# bme_radar.net
KiCad netlist of a schematic drawn in Altium Designer
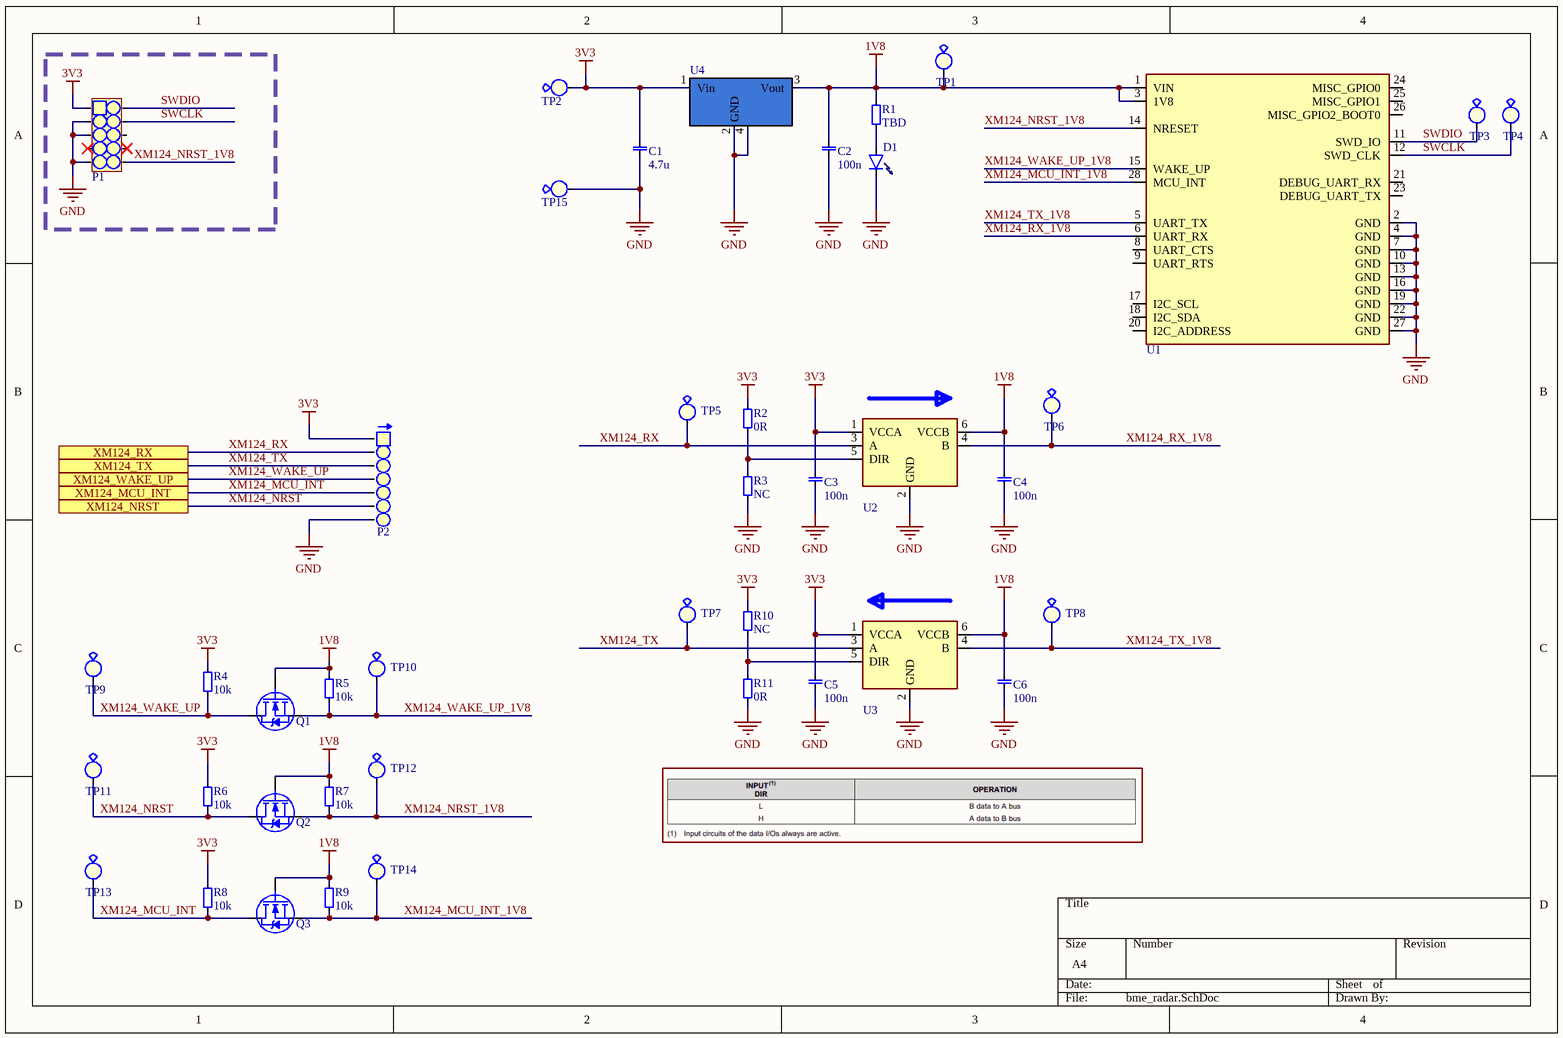
[diagram p0: bme_radar.SchDoc]

(export (version "E")
  (design (tool "Eeschema 10.0.6"))
  (components
    (comp (ref "C1")
      (value "4.7u")
      (footprint "0805, cap")
      (fields
        (field (name "MANUFACTURER PART NO") "CL21A475KAQNNNE")
        (field (name "Comment") "0805, capacitor")
      )
      (libsource (lib "jclib") (part "0805, capacitor"))
    )
    (comp (ref "C2")
      (value "100n")
      (footprint "0805, cap")
      (fields
        (field (name "MANUFACTURER PART NO") "C0805C104M5RAC7800")
        (field (name "Comment") "0805, capacitor")
      )
      (libsource (lib "jclib") (part "0805, capacitor"))
    )
    (comp (ref "C3")
      (value "100n")
      (footprint "0402 CAP")
      (fields
        (field (name "MANUFACTURER PART NO") "GRM155R62A104KE14D")
        (field (name "Comment") "0603, capacitor")
      )
      (libsource (lib "jclib") (part "0603, capacitor"))
    )
    (comp (ref "C4")
      (value "100n")
      (footprint "0402 CAP")
      (fields
        (field (name "MANUFACTURER PART NO") "GRM155R62A104KE14D")
        (field (name "Comment") "0603, capacitor")
      )
      (libsource (lib "jclib") (part "0603, capacitor"))
    )
    (comp (ref "C5")
      (value "100n")
      (footprint "0402 CAP")
      (fields
        (field (name "MANUFACTURER PART NO") "GRM155R62A104KE14D")
        (field (name "Comment") "0603, capacitor")
      )
      (libsource (lib "jclib") (part "0603, capacitor"))
    )
    (comp (ref "C6")
      (value "100n")
      (footprint "0402 CAP")
      (fields
        (field (name "MANUFACTURER PART NO") "GRM155R62A104KE14D")
        (field (name "Comment") "0603, capacitor")
      )
      (libsource (lib "jclib") (part "0603, capacitor"))
    )
    (comp (ref "D1")
      (value "0603, LED")
      (footprint "0603 LED")
      (fields (field (name "MANUFACTURER PART NO") "150060SS75003"))
      (libsource (lib "jclib") (part "0603, LED"))
    )
    (comp (ref "P1")
      (value "ARM 10 pin SWD")
      (footprint "FTSH-105-01-L-DV-K even odd")
      (description "1.27mm, PH")
      (fields (field (name "MANUFACTURER PART NO") "FTSH-105-01-L-DV-K"))
      (libsource (lib "jclib") (part "ARM 10 pin SWD"))
    )
    (comp (ref "P2")
      (value "1x7 Pin Header R/A")
      (footprint "1x7_HEADER_R/A")
      (description "1.27 mm")
      (fields (field (name "MANUFACTURER PART NO") "TMS-107-01-L-S-RA"))
      (libsource (lib "jclib") (part "1x7 Pin Header R/A"))
    )
    (comp (ref "Q1")
      (value "BSS138")
      (footprint "SOT323")
      (description "N-Channel Logic Level Enhancement Mode Field Effect Transistor")
      (fields (field (name "MANUFACTURER PART NO") "BSS138W-7-F"))
      (libsource (lib "jclib") (part "BSS138"))
    )
    (comp (ref "Q2")
      (value "BSS138")
      (footprint "SOT323")
      (description "N-Channel Logic Level Enhancement Mode Field Effect Transistor")
      (fields (field (name "MANUFACTURER PART NO") "BSS138W-7-F"))
      (libsource (lib "jclib") (part "BSS138"))
    )
    (comp (ref "Q3")
      (value "BSS138")
      (footprint "SOT323")
      (description "N-Channel Logic Level Enhancement Mode Field Effect Transistor")
      (fields (field (name "MANUFACTURER PART NO") "BSS138W-7-F"))
      (libsource (lib "jclib") (part "BSS138"))
    )
    (comp (ref "R1")
      (value "TBD")
      (footprint "0603")
      (fields (field (name "Comment") "0603, resistor"))
      (libsource (lib "jclib") (part "0603, resistor"))
    )
    (comp (ref "R2")
      (value "0R")
      (footprint "0402 res")
      (fields
        (field (name "MANUFACTURER PART NO") "RMCF0402ZT0R00")
        (field (name "Comment") "0603, resistor")
      )
      (libsource (lib "jclib") (part "0603, resistor"))
    )
    (comp (ref "R3")
      (value "NC")
      (footprint "0402 res")
      (fields
        (field (name "MANUFACTURER PART NO") "RMCF0402ZT0R00")
        (field (name "Comment") "0603, resistor")
      )
      (libsource (lib "jclib") (part "0603, resistor"))
    )
    (comp (ref "R4")
      (value "10k")
      (footprint "0603")
      (fields
        (field (name "MANUFACTURER PART NO") "CR0603-16W-1002FT")
        (field (name "Comment") "0603, resistor")
      )
      (libsource (lib "jclib") (part "0603, resistor"))
    )
    (comp (ref "R5")
      (value "10k")
      (footprint "0603")
      (fields
        (field (name "MANUFACTURER PART NO") "CR0603-16W-1002FT")
        (field (name "Comment") "0603, resistor")
      )
      (libsource (lib "jclib") (part "0603, resistor"))
    )
    (comp (ref "R6")
      (value "10k")
      (footprint "0603")
      (fields
        (field (name "MANUFACTURER PART NO") "CR0603-16W-1002FT")
        (field (name "Comment") "0603, resistor")
      )
      (libsource (lib "jclib") (part "0603, resistor"))
    )
    (comp (ref "R7")
      (value "10k")
      (footprint "0603")
      (fields
        (field (name "MANUFACTURER PART NO") "CR0603-16W-1002FT")
        (field (name "Comment") "0603, resistor")
      )
      (libsource (lib "jclib") (part "0603, resistor"))
    )
    (comp (ref "R8")
      (value "10k")
      (footprint "0603")
      (fields
        (field (name "MANUFACTURER PART NO") "CR0603-16W-1002FT")
        (field (name "Comment") "0603, resistor")
      )
      (libsource (lib "jclib") (part "0603, resistor"))
    )
    (comp (ref "R9")
      (value "10k")
      (footprint "0603")
      (fields
        (field (name "MANUFACTURER PART NO") "CR0603-16W-1002FT")
        (field (name "Comment") "0603, resistor")
      )
      (libsource (lib "jclib") (part "0603, resistor"))
    )
    (comp (ref "R10")
      (value "NC")
      (footprint "0402 res")
      (fields
        (field (name "MANUFACTURER PART NO") "RMCF0402ZT0R00")
        (field (name "Comment") "0603, resistor")
      )
      (libsource (lib "jclib") (part "0603, resistor"))
    )
    (comp (ref "R11")
      (value "0R")
      (footprint "0402 res")
      (fields
        (field (name "MANUFACTURER PART NO") "RMCF0402ZT0R00")
        (field (name "Comment") "0603, resistor")
      )
      (libsource (lib "jclib") (part "0603, resistor"))
    )
    (comp (ref "TP1")
      (value "Test Point")
      (footprint "TESTPOINT_SMD")
      (libsource (lib "jclib") (part "Test Point"))
    )
    (comp (ref "TP2")
      (value "Test Point")
      (footprint "TESTPOINT_SMD")
      (libsource (lib "jclib") (part "Test Point"))
    )
    (comp (ref "TP3")
      (value "Test Point")
      (footprint "TESTPOINT_SMD")
      (libsource (lib "jclib") (part "Test Point"))
    )
    (comp (ref "TP4")
      (value "Test Point")
      (footprint "TESTPOINT_SMD")
      (libsource (lib "jclib") (part "Test Point"))
    )
    (comp (ref "TP5")
      (value "Test Point")
      (footprint "TESTPOINT_SMD")
      (libsource (lib "jclib") (part "Test Point"))
    )
    (comp (ref "TP6")
      (value "Test Point")
      (footprint "TESTPOINT_SMD")
      (libsource (lib "jclib") (part "Test Point"))
    )
    (comp (ref "TP7")
      (value "Test Point")
      (footprint "TESTPOINT_SMD")
      (libsource (lib "jclib") (part "Test Point"))
    )
    (comp (ref "TP8")
      (value "Test Point")
      (footprint "TESTPOINT_SMD")
      (libsource (lib "jclib") (part "Test Point"))
    )
    (comp (ref "TP9")
      (value "Test Point")
      (footprint "TESTPOINT_SMD")
      (libsource (lib "jclib") (part "Test Point"))
    )
    (comp (ref "TP10")
      (value "Test Point")
      (footprint "TESTPOINT_SMD")
      (libsource (lib "jclib") (part "Test Point"))
    )
    (comp (ref "TP11")
      (value "Test Point")
      (footprint "TESTPOINT_SMD")
      (libsource (lib "jclib") (part "Test Point"))
    )
    (comp (ref "TP12")
      (value "Test Point")
      (footprint "TESTPOINT_SMD")
      (libsource (lib "jclib") (part "Test Point"))
    )
    (comp (ref "TP13")
      (value "Test Point")
      (footprint "TESTPOINT_SMD")
      (libsource (lib "jclib") (part "Test Point"))
    )
    (comp (ref "TP14")
      (value "Test Point")
      (footprint "TESTPOINT_SMD")
      (libsource (lib "jclib") (part "Test Point"))
    )
    (comp (ref "TP15")
      (value "Test Point")
      (footprint "TESTPOINT_SMD")
      (libsource (lib "jclib") (part "Test Point"))
    )
    (comp (ref "U1")
      (value "XM124")
      (footprint "XM124")
      (description "RF IC Sensor Radar 60GHz")
      (libsource (lib "jclib") (part "XM124"))
    )
    (comp (ref "U2")
      (value "SN74AXC1T45-Q1")
      (footprint "SOT65P210X110-6N")
      (fields (field (name "MANUFACTURER PART NO") "SN74AXC1T45QDCKRQ1"))
      (libsource (lib "amber_microradar_lib") (part "SN74AXC1T45-Q1"))
    )
    (comp (ref "U3")
      (value "SN74AXC1T45-Q1")
      (footprint "SOT65P210X110-6N")
      (fields (field (name "MANUFACTURER PART NO") "SN74AXC1T45QDCKRQ1"))
      (libsource (lib "amber_microradar_lib") (part "SN74AXC1T45-Q1"))
    )
    (comp (ref "U4")
      (value "3.3V Reg")
      (footprint "SOT223")
      (description "1 A, Positive Fixed-Voltage, Low-ccDropout Regulator")
      (fields (field (name "MANUFACTURER PART NO") "MCP1826ST-1802E/DB"))
      (libsource (lib "jclib") (part "MCP1826S"))
    )
  )
  (nets
    (net (code "1") (name "/SWCLK") (class "Default")
      (node (ref "P1") (pin "4") (pinfunction "4_4") (pintype "passive"))
      (node (ref "TP4") (pin "0") (pinfunction "0_0") (pintype "passive"))
      (node (ref "U1") (pin "12") (pinfunction "SWD_CLK_12") (pintype "passive"))
    )
    (net (code "2") (name "/SWDIO") (class "Default")
      (node (ref "P1") (pin "2") (pinfunction "2_2") (pintype "passive"))
      (node (ref "TP3") (pin "0") (pinfunction "0_0") (pintype "passive"))
      (node (ref "U1") (pin "11") (pinfunction "SWD_IO_11") (pintype "passive"))
    )
    (net (code "3") (name "/XM124_MCU_INT") (class "Default")
      (node (ref "P2") (pin "5") (pinfunction "5_5") (pintype "passive"))
      (node (ref "Q3") (pin "2") (pinfunction "D_2") (pintype "passive"))
      (node (ref "R8") (pin "0") (pinfunction "0_0") (pintype "passive"))
      (node (ref "TP13") (pin "0") (pinfunction "0_0") (pintype "passive"))
    )
    (net (code "4") (name "/XM124_MCU_INT_1V8") (class "Default")
      (node (ref "Q3") (pin "3") (pinfunction "S_3") (pintype "passive"))
      (node (ref "R9") (pin "0") (pinfunction "0_0") (pintype "passive"))
      (node (ref "TP14") (pin "0") (pinfunction "0_0") (pintype "passive"))
      (node (ref "U1") (pin "28") (pinfunction "MCU_INT_28") (pintype "passive"))
    )
    (net (code "5") (name "/XM124_NRST") (class "Default")
      (node (ref "P2") (pin "6") (pinfunction "6_6") (pintype "passive"))
      (node (ref "Q2") (pin "2") (pinfunction "D_2") (pintype "passive"))
      (node (ref "R6") (pin "0") (pinfunction "0_0") (pintype "passive"))
      (node (ref "TP11") (pin "0") (pinfunction "0_0") (pintype "passive"))
    )
    (net (code "6") (name "/XM124_NRST_1V8") (class "Default")
      (node (ref "P1") (pin "10") (pinfunction "10_10") (pintype "passive"))
      (node (ref "Q2") (pin "3") (pinfunction "S_3") (pintype "passive"))
      (node (ref "R7") (pin "0") (pinfunction "0_0") (pintype "passive"))
      (node (ref "TP12") (pin "0") (pinfunction "0_0") (pintype "passive"))
      (node (ref "U1") (pin "14") (pinfunction "NRESET_14") (pintype "passive"))
    )
    (net (code "7") (name "/XM124_RX") (class "Default")
      (node (ref "P2") (pin "2") (pinfunction "2_2") (pintype "passive"))
      (node (ref "TP5") (pin "0") (pinfunction "0_0") (pintype "passive"))
      (node (ref "U2") (pin "3") (pinfunction "A_3") (pintype "passive"))
    )
    (net (code "8") (name "/XM124_RX_1V8") (class "Default")
      (node (ref "TP6") (pin "0") (pinfunction "0_0") (pintype "passive"))
      (node (ref "U1") (pin "6") (pinfunction "UART_RX_6") (pintype "passive"))
      (node (ref "U2") (pin "4") (pinfunction "B_4") (pintype "passive"))
    )
    (net (code "9") (name "/XM124_TX") (class "Default")
      (node (ref "P2") (pin "3") (pinfunction "3_3") (pintype "passive"))
      (node (ref "TP7") (pin "0") (pinfunction "0_0") (pintype "passive"))
      (node (ref "U3") (pin "3") (pinfunction "A_3") (pintype "passive"))
    )
    (net (code "10") (name "/XM124_TX_1V8") (class "Default")
      (node (ref "TP8") (pin "0") (pinfunction "0_0") (pintype "passive"))
      (node (ref "U1") (pin "5") (pinfunction "UART_TX_5") (pintype "passive"))
      (node (ref "U3") (pin "4") (pinfunction "B_4") (pintype "passive"))
    )
    (net (code "11") (name "/XM124_WAKE_UP") (class "Default")
      (node (ref "P2") (pin "4") (pinfunction "4_4") (pintype "passive"))
      (node (ref "Q1") (pin "2") (pinfunction "D_2") (pintype "passive"))
      (node (ref "R4") (pin "0") (pinfunction "0_0") (pintype "passive"))
      (node (ref "TP9") (pin "0") (pinfunction "0_0") (pintype "passive"))
    )
    (net (code "12") (name "/XM124_WAKE_UP_1V8") (class "Default")
      (node (ref "Q1") (pin "3") (pinfunction "S_3") (pintype "passive"))
      (node (ref "R5") (pin "0") (pinfunction "0_0") (pintype "passive"))
      (node (ref "TP10") (pin "0") (pinfunction "0_0") (pintype "passive"))
      (node (ref "U1") (pin "15") (pinfunction "WAKE_UP_15") (pintype "passive"))
    )
    (net (code "13") (name "1V8") (class "Default")
      (node (ref "C2") (pin "1") (pinfunction "1_1") (pintype "passive"))
      (node (ref "C4") (pin "1") (pinfunction "1_1") (pintype "passive"))
      (node (ref "C6") (pin "1") (pinfunction "1_1") (pintype "passive"))
      (node (ref "Q1") (pin "1") (pinfunction "G_1") (pintype "passive"))
      (node (ref "Q2") (pin "1") (pinfunction "G_1") (pintype "passive"))
      (node (ref "Q3") (pin "1") (pinfunction "G_1") (pintype "passive"))
      (node (ref "R1") (pin "1") (pinfunction "1_1") (pintype "passive"))
      (node (ref "R5") (pin "1") (pinfunction "1_1") (pintype "passive"))
      (node (ref "R7") (pin "1") (pinfunction "1_1") (pintype "passive"))
      (node (ref "R9") (pin "1") (pinfunction "1_1") (pintype "passive"))
      (node (ref "TP1") (pin "0") (pinfunction "0_0") (pintype "passive"))
      (node (ref "U1") (pin "1") (pinfunction "VIN_1") (pintype "passive"))
      (node (ref "U1") (pin "3") (pinfunction "1V8_3") (pintype "passive"))
      (node (ref "U2") (pin "6") (pinfunction "VCCB_6") (pintype "power_in"))
      (node (ref "U3") (pin "6") (pinfunction "VCCB_6") (pintype "power_in"))
      (node (ref "U4") (pin "3") (pinfunction "Vout_3") (pintype "passive"))
    )
    (net (code "14") (name "3V3") (class "Default")
      (node (ref "C1") (pin "1") (pinfunction "1_1") (pintype "passive"))
      (node (ref "C3") (pin "1") (pinfunction "1_1") (pintype "passive"))
      (node (ref "C5") (pin "1") (pinfunction "1_1") (pintype "passive"))
      (node (ref "P1") (pin "1") (pinfunction "1_1") (pintype "passive"))
      (node (ref "P2") (pin "1") (pinfunction "1_1") (pintype "passive"))
      (node (ref "R10") (pin "0") (pinfunction "0_0") (pintype "passive"))
      (node (ref "R2") (pin "0") (pinfunction "0_0") (pintype "passive"))
      (node (ref "R4") (pin "1") (pinfunction "1_1") (pintype "passive"))
      (node (ref "R6") (pin "1") (pinfunction "1_1") (pintype "passive"))
      (node (ref "R8") (pin "1") (pinfunction "1_1") (pintype "passive"))
      (node (ref "TP2") (pin "0") (pinfunction "0_0") (pintype "passive"))
      (node (ref "U2") (pin "1") (pinfunction "VCCA_1") (pintype "power_in"))
      (node (ref "U3") (pin "1") (pinfunction "VCCA_1") (pintype "power_in"))
      (node (ref "U4") (pin "1") (pinfunction "Vin_1") (pintype "passive"))
    )
    (net (code "15") (name "GND") (class "Default")
      (node (ref "C1") (pin "0") (pinfunction "0_0") (pintype "passive"))
      (node (ref "C2") (pin "0") (pinfunction "0_0") (pintype "passive"))
      (node (ref "C3") (pin "0") (pinfunction "0_0") (pintype "passive"))
      (node (ref "C4") (pin "0") (pinfunction "0_0") (pintype "passive"))
      (node (ref "C5") (pin "0") (pinfunction "0_0") (pintype "passive"))
      (node (ref "C6") (pin "0") (pinfunction "0_0") (pintype "passive"))
      (node (ref "D1") (pin "0") (pinfunction "Cathode_0") (pintype "passive"))
      (node (ref "P1") (pin "3") (pinfunction "3_3") (pintype "passive"))
      (node (ref "P1") (pin "5") (pinfunction "5_5") (pintype "passive"))
      (node (ref "P1") (pin "9") (pinfunction "9_9") (pintype "passive"))
      (node (ref "P2") (pin "7") (pinfunction "7_7") (pintype "passive"))
      (node (ref "R11") (pin "1") (pinfunction "1_1") (pintype "passive"))
      (node (ref "R3") (pin "1") (pinfunction "1_1") (pintype "passive"))
      (node (ref "TP15") (pin "0") (pinfunction "0_0") (pintype "passive"))
      (node (ref "U1") (pin "10") (pinfunction "GND_10") (pintype "passive"))
      (node (ref "U1") (pin "13") (pinfunction "GND_13") (pintype "passive"))
      (node (ref "U1") (pin "16") (pinfunction "GND_16") (pintype "passive"))
      (node (ref "U1") (pin "19") (pinfunction "GND_19") (pintype "passive"))
      (node (ref "U1") (pin "2") (pinfunction "GND_2") (pintype "passive"))
      (node (ref "U1") (pin "22") (pinfunction "GND_22") (pintype "passive"))
      (node (ref "U1") (pin "27") (pinfunction "GND_27") (pintype "passive"))
      (node (ref "U1") (pin "4") (pinfunction "GND_4") (pintype "passive"))
      (node (ref "U1") (pin "7") (pinfunction "GND_7") (pintype "passive"))
      (node (ref "U2") (pin "2") (pinfunction "GND_2") (pintype "power_in"))
      (node (ref "U3") (pin "2") (pinfunction "GND_2") (pintype "power_in"))
      (node (ref "U4") (pin "2") (pinfunction "GND_2") (pintype "passive"))
      (node (ref "U4") (pin "4") (pintype "passive"))
    )
    (net (code "16") (name "Net-(D1-Pad1)") (class "Default")
      (node (ref "D1") (pin "1") (pinfunction "1_1") (pintype "passive"))
      (node (ref "R1") (pin "0") (pinfunction "0_0") (pintype "passive"))
    )
    (net (code "17") (name "Net-(U2-DIR)") (class "Default")
      (node (ref "R2") (pin "1") (pinfunction "1_1") (pintype "passive"))
      (node (ref "R3") (pin "0") (pinfunction "0_0") (pintype "passive"))
      (node (ref "U2") (pin "5") (pinfunction "DIR_5") (pintype "passive"))
    )
    (net (code "18") (name "Net-(U3-DIR)") (class "Default")
      (node (ref "R10") (pin "1") (pinfunction "1_1") (pintype "passive"))
      (node (ref "R11") (pin "0") (pinfunction "0_0") (pintype "passive"))
      (node (ref "U3") (pin "5") (pinfunction "DIR_5") (pintype "passive"))
    )
    (net (code "19") (name "unconnected-(P1-Pad6)") (class "Default")
      (node (ref "P1") (pin "6") (pinfunction "6_6") (pintype "passive"))
    )
    (net (code "20") (name "unconnected-(P1-Pad7)") (class "Default")
      (node (ref "P1") (pin "7") (pinfunction "7_7") (pintype "passive+no_connect"))
    )
    (net (code "21") (name "unconnected-(P1-Pad8)") (class "Default")
      (node (ref "P1") (pin "8") (pinfunction "8_8") (pintype "passive+no_connect"))
    )
    (net (code "22") (name "unconnected-(U1-DEBUG_UART_RX-Pad21)") (class "Default")
      (node (ref "U1") (pin "21") (pinfunction "DEBUG_UART_RX_21") (pintype "passive"))
    )
    (net (code "23") (name "unconnected-(U1-DEBUG_UART_TX-Pad23)") (class "Default")
      (node (ref "U1") (pin "23") (pinfunction "DEBUG_UART_TX_23") (pintype "passive"))
    )
    (net (code "24") (name "unconnected-(U1-I2C_ADDRESS-Pad20)") (class "Default")
      (node (ref "U1") (pin "20") (pinfunction "I2C_ADDRESS_20") (pintype "passive"))
    )
    (net (code "25") (name "unconnected-(U1-I2C_SCL-Pad17)") (class "Default")
      (node (ref "U1") (pin "17") (pinfunction "I2C_SCL_17") (pintype "passive"))
    )
    (net (code "26") (name "unconnected-(U1-I2C_SDA-Pad18)") (class "Default")
      (node (ref "U1") (pin "18") (pinfunction "I2C_SDA_18") (pintype "passive"))
    )
    (net (code "27") (name "unconnected-(U1-MISC_GPIO0-Pad24)") (class "Default")
      (node (ref "U1") (pin "24") (pinfunction "MISC_GPIO0_24") (pintype "passive"))
    )
    (net (code "28") (name "unconnected-(U1-MISC_GPIO1-Pad25)") (class "Default")
      (node (ref "U1") (pin "25") (pinfunction "MISC_GPIO1_25") (pintype "passive"))
    )
    (net (code "29") (name "unconnected-(U1-MISC_GPIO2_BOOT0-Pad26)") (class "Default")
      (node (ref "U1") (pin "26") (pinfunction "MISC_GPIO2_BOOT0_26") (pintype "passive"))
    )
    (net (code "30") (name "unconnected-(U1-UART_CTS-Pad8)") (class "Default")
      (node (ref "U1") (pin "8") (pinfunction "UART_CTS_8") (pintype "passive"))
    )
    (net (code "31") (name "unconnected-(U1-UART_RTS-Pad9)") (class "Default")
      (node (ref "U1") (pin "9") (pinfunction "UART_RTS_9") (pintype "passive"))
    )
  )
)
